# KC_BaseBoard4CompareTest-V0_31.net
KiCad netlist of a schematic drawn in Altium Designer
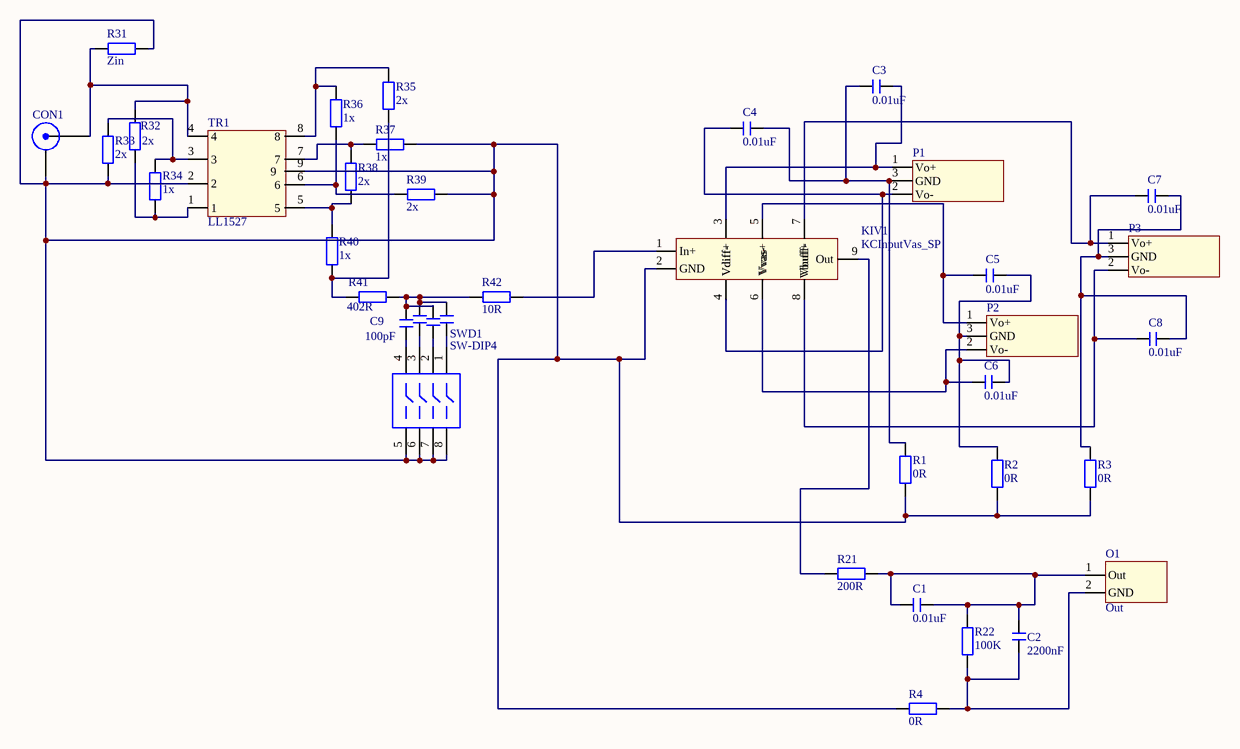
[diagram p0: KC_BaseBoard4CompareTest-V0.31.SchDoc]

(export (version "E")
  (design (tool "Eeschema 10.0.6"))
  (components
    (comp (ref "C1")
      (value "0.01uF")
      (footprint "CBB 6.3*6.3*5")
      (description "CBB电容")
      (fields (field (name "版权归属") "源创客"))
      (libsource (lib "电阻-电容-电感") (part "C-CBB"))
    )
    (comp (ref "C2")
      (value "2200nF")
      (footprint "CBB 6.3*6.3*5")
      (description "CBB电容")
      (fields (field (name "版权归属") "源创客"))
      (libsource (lib "电阻-电容-电感") (part "C-CBB"))
    )
    (comp (ref "C3")
      (value "0.01uF")
      (footprint "CBB 6.3*6.3*5")
      (description "CBB电容")
      (fields (field (name "版权归属") "源创客"))
      (libsource (lib "电阻-电容-电感") (part "C-CBB"))
    )
    (comp (ref "C4")
      (value "0.01uF")
      (footprint "CBB 6.3*6.3*5")
      (description "CBB电容")
      (fields (field (name "版权归属") "源创客"))
      (libsource (lib "电阻-电容-电感") (part "C-CBB"))
    )
    (comp (ref "C5")
      (value "0.01uF")
      (footprint "CBB 6.3*6.3*5")
      (description "CBB电容")
      (fields (field (name "版权归属") "源创客"))
      (libsource (lib "电阻-电容-电感") (part "C-CBB"))
    )
    (comp (ref "C6")
      (value "0.01uF")
      (footprint "CBB 6.3*6.3*5")
      (description "CBB电容")
      (fields (field (name "版权归属") "源创客"))
      (libsource (lib "电阻-电容-电感") (part "C-CBB"))
    )
    (comp (ref "C7")
      (value "0.01uF")
      (footprint "CBB 6.3*6.3*5")
      (description "CBB电容")
      (fields (field (name "版权归属") "源创客"))
      (libsource (lib "电阻-电容-电感") (part "C-CBB"))
    )
    (comp (ref "C8")
      (value "0.01uF")
      (footprint "CBB 6.3*6.3*5")
      (description "CBB电容")
      (fields (field (name "版权归属") "源创客"))
      (libsource (lib "电阻-电容-电感") (part "C-CBB"))
    )
    (comp (ref "C9")
      (value "100pF")
      (footprint "CBB 6.3*6.3*5")
      (description "CBB电容")
      (fields (field (name "版权归属") "源创客"))
      (libsource (lib "电阻-电容-电感") (part "C-CBB"))
    )
    (comp (ref "C10")
      (value "100pF")
      (footprint "CBB 6.3*6.3*5")
      (description "CBB电容")
      (fields (field (name "版权归属") "源创客"))
      (libsource (lib "电阻-电容-电感") (part "C-CBB"))
    )
    (comp (ref "C11")
      (value "100pF")
      (footprint "CBB 6.3*6.3*5")
      (description "CBB电容")
      (fields (field (name "版权归属") "源创客"))
      (libsource (lib "电阻-电容-电感") (part "C-CBB"))
    )
    (comp (ref "C12")
      (value "20pF")
      (footprint "CBB 6.3*6.3*5")
      (description "CBB电容")
      (fields (field (name "版权归属") "源创客"))
      (libsource (lib "电阻-电容-电感") (part "C-CBB"))
    )
    (comp (ref "CON1")
      (value "RCA")
      (footprint "RCA-RJ255")
      (description "RCA Connector")
      (fields (field (name "PUBLISHER") "Altium Limited"))
      (libsource (lib "Connectors") (part "RCA"))
    )
    (comp (ref "KIV1")
      (value "KCInputVas_SP")
      (footprint "KCIn_VAS_SP_M4")
      (description "King Cello Input Stage and VAS for Seperated Power")
      (libsource (lib "KC_amp") (part "KCInputVas_SP"))
    )
    (comp (ref "O1")
      (value "Out")
      (footprint "Signal_Terminal")
      (description "Signal Out")
      (libsource (lib "KC_amp") (part "Signal_Out"))
    )
    (comp (ref "P1")
      (value "Vdiff")
      (footprint "KC_MBPowerReg4Compare-1.5mm")
      (description "King Cello Compare Test Power")
      (libsource (lib "KC_amp") (part "MainBoardPowerRegulator4CompareTest"))
    )
    (comp (ref "P2")
      (value "Vvas")
      (footprint "KC_MBPowerReg4Compare-1.5mm")
      (description "King Cello Compare Test Power")
      (libsource (lib "KC_amp") (part "MainBoardPowerRegulator4CompareTest"))
    )
    (comp (ref "P3")
      (value "Vbuff")
      (footprint "KC_MBPowerReg4Compare-1.5mm")
      (description "King Cello Compare Test Power")
      (libsource (lib "KC_amp") (part "MainBoardPowerRegulator4CompareTest"))
    )
    (comp (ref "R1")
      (value "0R")
      (footprint "RS 1/4W")
      (description "直插色环电阻")
      (fields (field (name "版权归属") "源创客"))
      (libsource (lib "电阻-电容-电感") (part "R-CRR"))
    )
    (comp (ref "R2")
      (value "0R")
      (footprint "RS 1/4W")
      (description "直插色环电阻")
      (fields (field (name "版权归属") "源创客"))
      (libsource (lib "电阻-电容-电感") (part "R-CRR"))
    )
    (comp (ref "R3")
      (value "0R")
      (footprint "RS 1/4W")
      (description "直插色环电阻")
      (fields (field (name "版权归属") "源创客"))
      (libsource (lib "电阻-电容-电感") (part "R-CRR"))
    )
    (comp (ref "R4")
      (value "0R")
      (footprint "RS 1/4W")
      (description "直插色环电阻")
      (fields (field (name "版权归属") "源创客"))
      (libsource (lib "电阻-电容-电感") (part "R-CRR"))
    )
    (comp (ref "R21")
      (value "200R")
      (footprint "RS 1/4W")
      (description "直插色环电阻")
      (fields (field (name "版权归属") "源创客"))
      (libsource (lib "电阻-电容-电感") (part "R-CRR"))
    )
    (comp (ref "R22")
      (value "100K")
      (footprint "RS 1/4W")
      (description "直插色环电阻")
      (fields (field (name "版权归属") "源创客"))
      (libsource (lib "电阻-电容-电感") (part "R-CRR"))
    )
    (comp (ref "R31")
      (value "Zin")
      (footprint "RS 1/4W")
      (description "直插色环电阻")
      (fields (field (name "版权归属") "源创客"))
      (libsource (lib "电阻-电容-电感") (part "R-CRR"))
    )
    (comp (ref "R32")
      (value "2x")
      (footprint "RS 1/4W")
      (description "直插色环电阻")
      (fields (field (name "版权归属") "源创客"))
      (libsource (lib "电阻-电容-电感") (part "R-CRR"))
    )
    (comp (ref "R33")
      (value "2x")
      (footprint "RS 1/4W")
      (description "直插色环电阻")
      (fields (field (name "版权归属") "源创客"))
      (libsource (lib "电阻-电容-电感") (part "R-CRR"))
    )
    (comp (ref "R34")
      (value "1x")
      (footprint "RS 1/4W")
      (description "直插色环电阻")
      (fields (field (name "版权归属") "源创客"))
      (libsource (lib "电阻-电容-电感") (part "R-CRR"))
    )
    (comp (ref "R35")
      (value "2x")
      (footprint "RS 1/4W")
      (description "直插色环电阻")
      (fields (field (name "版权归属") "源创客"))
      (libsource (lib "电阻-电容-电感") (part "R-CRR"))
    )
    (comp (ref "R36")
      (value "1x")
      (footprint "RS 1/4W")
      (description "直插色环电阻")
      (fields (field (name "版权归属") "源创客"))
      (libsource (lib "电阻-电容-电感") (part "R-CRR"))
    )
    (comp (ref "R37")
      (value "1x")
      (footprint "RS 1/4W")
      (description "直插色环电阻")
      (fields (field (name "版权归属") "源创客"))
      (libsource (lib "电阻-电容-电感") (part "R-CRR"))
    )
    (comp (ref "R38")
      (value "2x")
      (footprint "RS 1/4W")
      (description "直插色环电阻")
      (fields (field (name "版权归属") "源创客"))
      (libsource (lib "电阻-电容-电感") (part "R-CRR"))
    )
    (comp (ref "R39")
      (value "2x")
      (footprint "RS 1/4W")
      (description "直插色环电阻")
      (fields (field (name "版权归属") "源创客"))
      (libsource (lib "电阻-电容-电感") (part "R-CRR"))
    )
    (comp (ref "R40")
      (value "1x")
      (footprint "RS 1/4W")
      (description "直插色环电阻")
      (fields (field (name "版权归属") "源创客"))
      (libsource (lib "电阻-电容-电感") (part "R-CRR"))
    )
    (comp (ref "R41")
      (value "402R")
      (footprint "RS 1/4W")
      (description "直插色环电阻")
      (fields (field (name "版权归属") "源创客"))
      (libsource (lib "电阻-电容-电感") (part "R-CRR"))
    )
    (comp (ref "R42")
      (value "10R")
      (footprint "RS 1/4W")
      (description "直插色环电阻")
      (fields (field (name "版权归属") "源创客"))
      (libsource (lib "电阻-电容-电感") (part "R-CRR"))
    )
    (comp (ref "SWD1")
      (value "SW-DIP4")
      (footprint "DIP-8")
      (description "DIP Switch")
      (fields (field (name "PUBLISHER") "Altium Limited"))
      (libsource (lib "Miscellaneous Devices") (part "SW-DIP4"))
    )
    (comp (ref "TR1")
      (value "LL1527")
      (footprint "LL1527")
      (description "Lundahl LL1527")
      (libsource (lib "KC_amp") (part "LL1527"))
    )
  )
  (nets
    (net (code "1") (name "Net-(C9-Pad1)") (class "Default")
      (node (ref "C9") (pin "1") (pinfunction "1_1") (pintype "passive"))
      (node (ref "SWD1") (pin "4") (pinfunction "4_4") (pintype "passive"))
    )
    (net (code "2") (name "Net-(C10-Pad1)") (class "Default")
      (node (ref "C10") (pin "1") (pinfunction "1_1") (pintype "passive"))
      (node (ref "SWD1") (pin "3") (pinfunction "3_3") (pintype "passive"))
    )
    (net (code "3") (name "Net-(C10-Pad2)") (class "Default")
      (node (ref "C10") (pin "2") (pinfunction "2_2") (pintype "passive"))
      (node (ref "C11") (pin "2") (pinfunction "2_2") (pintype "passive"))
      (node (ref "C12") (pin "2") (pinfunction "2_2") (pintype "passive"))
      (node (ref "C9") (pin "2") (pinfunction "2_2") (pintype "passive"))
      (node (ref "R41") (pin "2") (pinfunction "2_2") (pintype "passive"))
      (node (ref "R42") (pin "1") (pinfunction "1_1") (pintype "passive"))
    )
    (net (code "4") (name "Net-(C11-Pad1)") (class "Default")
      (node (ref "C11") (pin "1") (pinfunction "1_1") (pintype "passive"))
      (node (ref "SWD1") (pin "2") (pinfunction "2_2") (pintype "passive"))
    )
    (net (code "5") (name "Net-(C12-Pad1)") (class "Default")
      (node (ref "C12") (pin "1") (pinfunction "1_1") (pintype "passive"))
      (node (ref "SWD1") (pin "1") (pinfunction "1_1") (pintype "passive"))
    )
    (net (code "6") (name "Net-(CON1-X)") (class "Default")
      (node (ref "CON1") (pin "1") (pinfunction "X_1") (pintype "passive"))
      (node (ref "R31") (pin "1") (pinfunction "1_1") (pintype "passive"))
      (node (ref "R32") (pin "2") (pinfunction "2_2") (pintype "passive"))
      (node (ref "TR1") (pin "4") (pinfunction "4_4") (pintype "passive"))
    )
    (net (code "7") (name "Net-(CON1-Y)") (class "Default")
      (node (ref "CON1") (pin "2") (pinfunction "Y_2") (pintype "passive"))
      (node (ref "KIV1") (pin "2") (pinfunction "GND_2") (pintype "passive"))
      (node (ref "R1") (pin "1") (pinfunction "1_1") (pintype "passive"))
      (node (ref "R2") (pin "1") (pinfunction "1_1") (pintype "passive"))
      (node (ref "R3") (pin "1") (pinfunction "1_1") (pintype "passive"))
      (node (ref "R31") (pin "2") (pinfunction "2_2") (pintype "passive"))
      (node (ref "R33") (pin "1") (pinfunction "1_1") (pintype "passive"))
      (node (ref "R37") (pin "2") (pinfunction "2_2") (pintype "passive"))
      (node (ref "R39") (pin "2") (pinfunction "2_2") (pintype "passive"))
      (node (ref "R4") (pin "2") (pinfunction "2_2") (pintype "passive"))
      (node (ref "SWD1") (pin "5") (pinfunction "5_5") (pintype "passive"))
      (node (ref "SWD1") (pin "6") (pinfunction "6_6") (pintype "passive"))
      (node (ref "SWD1") (pin "7") (pinfunction "7_7") (pintype "passive"))
      (node (ref "SWD1") (pin "8") (pinfunction "8_8") (pintype "passive"))
      (node (ref "TR1") (pin "2") (pinfunction "2_2") (pintype "passive"))
      (node (ref "TR1") (pin "9") (pinfunction "9_9") (pintype "passive"))
    )
    (net (code "8") (name "Net-(KIV1-In+)") (class "Default")
      (node (ref "KIV1") (pin "1") (pinfunction "In+_1") (pintype "passive"))
      (node (ref "R42") (pin "2") (pinfunction "2_2") (pintype "passive"))
    )
    (net (code "9") (name "Net-(KIV1-Out)") (class "Default")
      (node (ref "KIV1") (pin "9") (pinfunction "Out_9") (pintype "passive"))
      (node (ref "R21") (pin "2") (pinfunction "2_2") (pintype "passive"))
    )
    (net (code "10") (name "Net-(KIV1-Vbuff+)") (class "Default")
      (node (ref "C7") (pin "1") (pinfunction "1_1") (pintype "passive"))
      (node (ref "KIV1") (pin "7") (pinfunction "Vbuff+_7") (pintype "passive"))
      (node (ref "P3") (pin "1") (pinfunction "Vo+_1") (pintype "passive"))
    )
    (net (code "11") (name "Net-(KIV1-Vbuff-)") (class "Default")
      (node (ref "C8") (pin "1") (pinfunction "1_1") (pintype "passive"))
      (node (ref "KIV1") (pin "8") (pinfunction "Vbuff-_8") (pintype "passive"))
      (node (ref "P3") (pin "2") (pinfunction "Vo-_2") (pintype "passive"))
    )
    (net (code "12") (name "Net-(KIV1-Vdiff+)") (class "Default")
      (node (ref "C3") (pin "2") (pinfunction "2_2") (pintype "passive"))
      (node (ref "KIV1") (pin "3") (pinfunction "Vdiff+_3") (pintype "passive"))
      (node (ref "P1") (pin "1") (pinfunction "Vo+_1") (pintype "passive"))
    )
    (net (code "13") (name "Net-(KIV1-Vdiff-)") (class "Default")
      (node (ref "C4") (pin "1") (pinfunction "1_1") (pintype "passive"))
      (node (ref "KIV1") (pin "4") (pinfunction "Vdiff-_4") (pintype "passive"))
      (node (ref "P1") (pin "2") (pinfunction "Vo-_2") (pintype "passive"))
    )
    (net (code "14") (name "Net-(KIV1-Vvas+)") (class "Default")
      (node (ref "C5") (pin "1") (pinfunction "1_1") (pintype "passive"))
      (node (ref "KIV1") (pin "5") (pinfunction "Vvas+_5") (pintype "passive"))
      (node (ref "P2") (pin "1") (pinfunction "Vo+_1") (pintype "passive"))
    )
    (net (code "15") (name "Net-(KIV1-Vvas-)") (class "Default")
      (node (ref "C6") (pin "1") (pinfunction "1_1") (pintype "passive"))
      (node (ref "KIV1") (pin "6") (pinfunction "Vvas-_6") (pintype "passive"))
      (node (ref "P2") (pin "2") (pinfunction "Vo-_2") (pintype "passive"))
    )
    (net (code "16") (name "Net-(O1-GND)") (class "Default")
      (node (ref "C2") (pin "2") (pinfunction "2_2") (pintype "passive"))
      (node (ref "O1") (pin "2") (pinfunction "GND_2") (pintype "passive"))
      (node (ref "R22") (pin "2") (pinfunction "2_2") (pintype "passive"))
      (node (ref "R4") (pin "1") (pinfunction "1_1") (pintype "passive"))
    )
    (net (code "17") (name "Net-(O1-Out)") (class "Default")
      (node (ref "C1") (pin "1") (pinfunction "1_1") (pintype "passive"))
      (node (ref "C1") (pin "2") (pinfunction "2_2") (pintype "passive"))
      (node (ref "C2") (pin "1") (pinfunction "1_1") (pintype "passive"))
      (node (ref "O1") (pin "1") (pinfunction "Out_1") (pintype "passive"))
      (node (ref "R21") (pin "1") (pinfunction "1_1") (pintype "passive"))
      (node (ref "R22") (pin "1") (pinfunction "1_1") (pintype "passive"))
    )
    (net (code "18") (name "Net-(P1-GND)") (class "Default")
      (node (ref "C3") (pin "1") (pinfunction "1_1") (pintype "passive"))
      (node (ref "C4") (pin "2") (pinfunction "2_2") (pintype "passive"))
      (node (ref "P1") (pin "3") (pinfunction "GND_3") (pintype "passive"))
      (node (ref "R1") (pin "2") (pinfunction "2_2") (pintype "passive"))
    )
    (net (code "19") (name "Net-(P2-GND)") (class "Default")
      (node (ref "C5") (pin "2") (pinfunction "2_2") (pintype "passive"))
      (node (ref "C6") (pin "2") (pinfunction "2_2") (pintype "passive"))
      (node (ref "P2") (pin "3") (pinfunction "GND_3") (pintype "passive"))
      (node (ref "R2") (pin "2") (pinfunction "2_2") (pintype "passive"))
    )
    (net (code "20") (name "Net-(P3-GND)") (class "Default")
      (node (ref "C7") (pin "2") (pinfunction "2_2") (pintype "passive"))
      (node (ref "C8") (pin "2") (pinfunction "2_2") (pintype "passive"))
      (node (ref "P3") (pin "3") (pinfunction "GND_3") (pintype "passive"))
      (node (ref "R3") (pin "2") (pinfunction "2_2") (pintype "passive"))
    )
    (net (code "21") (name "Net-(R32-Pad1)") (class "Default")
      (node (ref "R32") (pin "1") (pinfunction "1_1") (pintype "passive"))
      (node (ref "R34") (pin "1") (pinfunction "1_1") (pintype "passive"))
      (node (ref "TR1") (pin "1") (pinfunction "1_1") (pintype "passive"))
    )
    (net (code "22") (name "Net-(R33-Pad2)") (class "Default")
      (node (ref "R33") (pin "2") (pinfunction "2_2") (pintype "passive"))
      (node (ref "R34") (pin "2") (pinfunction "2_2") (pintype "passive"))
      (node (ref "TR1") (pin "3") (pinfunction "3_3") (pintype "passive"))
    )
    (net (code "23") (name "Net-(R35-Pad1)") (class "Default")
      (node (ref "R35") (pin "1") (pinfunction "1_1") (pintype "passive"))
      (node (ref "R40") (pin "1") (pinfunction "1_1") (pintype "passive"))
      (node (ref "R41") (pin "1") (pinfunction "1_1") (pintype "passive"))
    )
    (net (code "24") (name "Net-(R35-Pad2)") (class "Default")
      (node (ref "R35") (pin "2") (pinfunction "2_2") (pintype "passive"))
      (node (ref "R36") (pin "2") (pinfunction "2_2") (pintype "passive"))
      (node (ref "TR1") (pin "8") (pinfunction "8_8") (pintype "passive"))
    )
    (net (code "25") (name "Net-(R36-Pad1)") (class "Default")
      (node (ref "R36") (pin "1") (pinfunction "1_1") (pintype "passive"))
      (node (ref "R39") (pin "1") (pinfunction "1_1") (pintype "passive"))
      (node (ref "TR1") (pin "6") (pinfunction "6_6") (pintype "passive"))
    )
    (net (code "26") (name "Net-(R37-Pad1)") (class "Default")
      (node (ref "R37") (pin "1") (pinfunction "1_1") (pintype "passive"))
      (node (ref "R38") (pin "2") (pinfunction "2_2") (pintype "passive"))
      (node (ref "TR1") (pin "7") (pinfunction "7_7") (pintype "passive"))
    )
    (net (code "27") (name "Net-(R38-Pad1)") (class "Default")
      (node (ref "R38") (pin "1") (pinfunction "1_1") (pintype "passive"))
      (node (ref "R40") (pin "2") (pinfunction "2_2") (pintype "passive"))
      (node (ref "TR1") (pin "5") (pinfunction "5_5") (pintype "passive"))
    )
  )
)
